# CPLD.net
KiCad netlist of a schematic drawn in Altium Designer
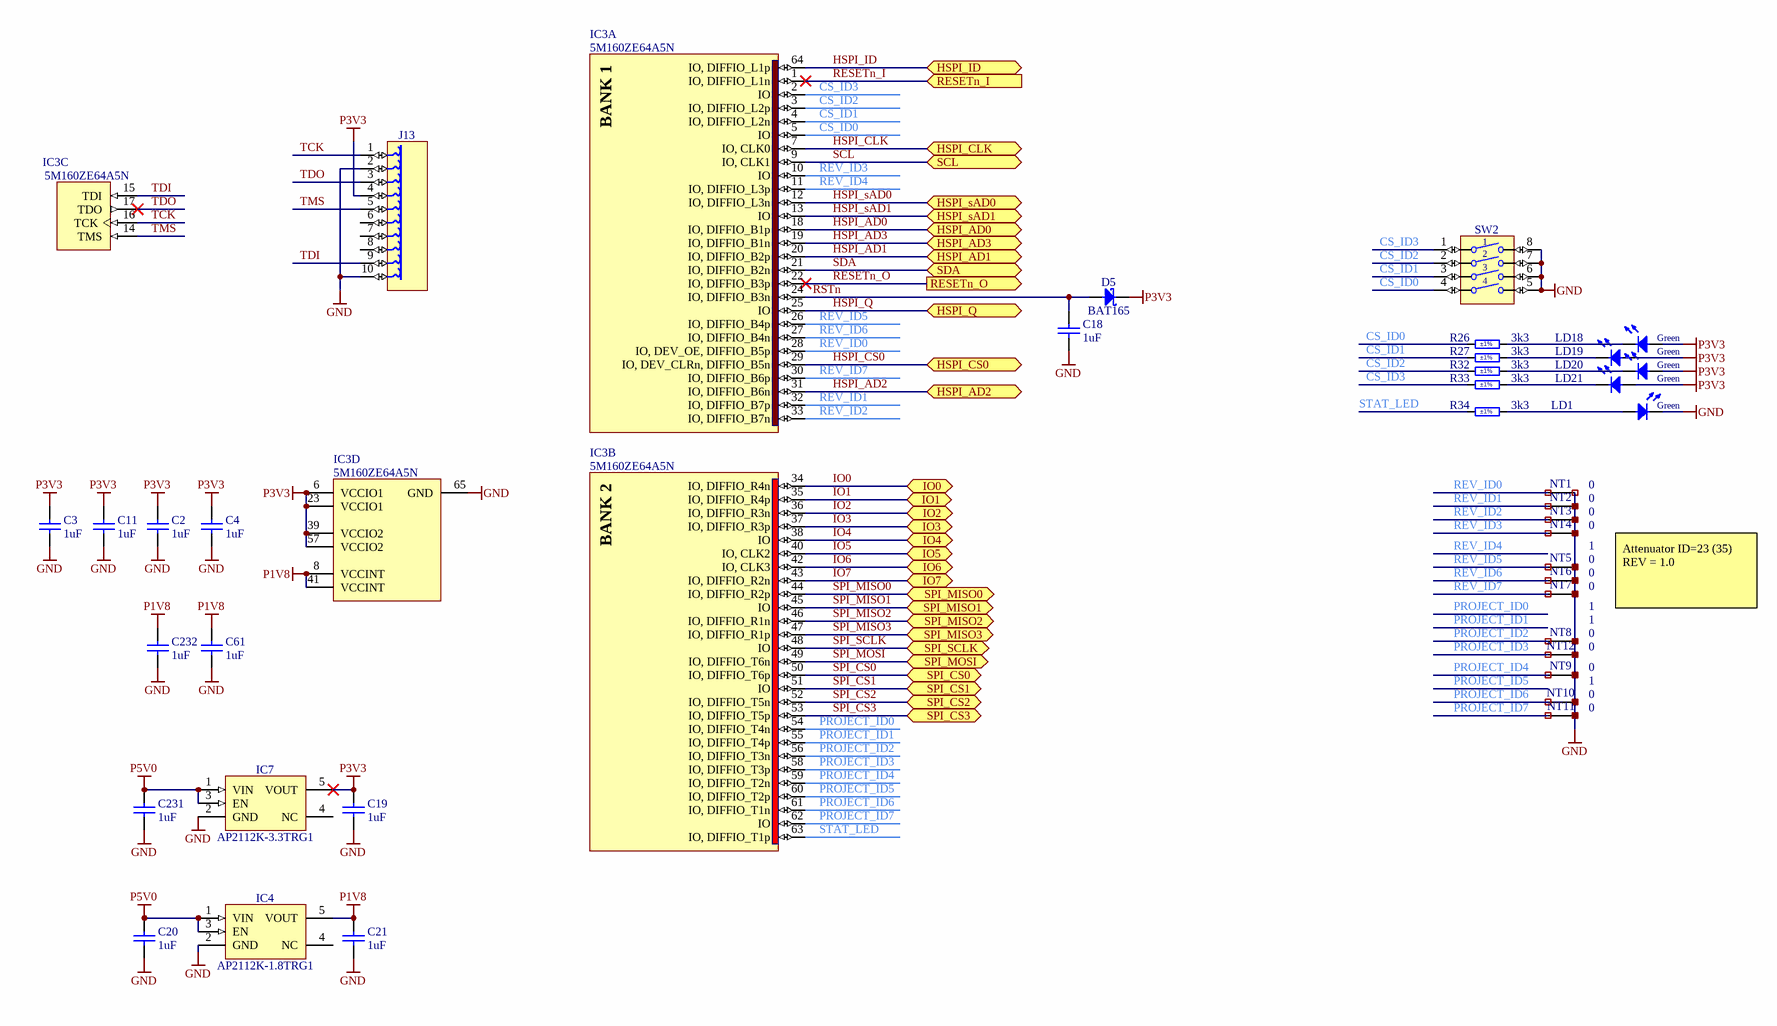
[diagram p0: CPLD.SchDoc]

(export (version "E")
  (design (tool "Eeschema 10.0.6"))
  (components
    (comp (ref "C2")
      (value "1uF")
      (footprint "CAPC1005X55N")
      (description "Non-polarised capacitor")
      (fields
        (field (name "PART NUMBER") "CC0402_1UF_16V_10%_X5R")
        (field (name "VOLTAGE") "16V")
        (field (name "AUTHOR") "CERN DEM JLC")
      )
      (libsource (lib "Capacitors") (part "Capacitor - non polarized"))
    )
    (comp (ref "C3")
      (value "1uF")
      (footprint "CAPC1005X55N")
      (description "Non-polarised capacitor")
      (fields
        (field (name "PART NUMBER") "CC0402_1UF_16V_10%_X5R")
        (field (name "VOLTAGE") "16V")
        (field (name "AUTHOR") "CERN DEM JLC")
      )
      (libsource (lib "Capacitors") (part "Capacitor - non polarized"))
    )
    (comp (ref "C4")
      (value "1uF")
      (footprint "CAPC1005X55N")
      (description "Non-polarised capacitor")
      (fields
        (field (name "PART NUMBER") "CC0402_1UF_16V_10%_X5R")
        (field (name "VOLTAGE") "16V")
        (field (name "AUTHOR") "CERN DEM JLC")
      )
      (libsource (lib "Capacitors") (part "Capacitor - non polarized"))
    )
    (comp (ref "C11")
      (value "1uF")
      (footprint "CAPC1005X55N")
      (description "Non-polarised capacitor")
      (fields
        (field (name "PART NUMBER") "CC0402_1UF_16V_10%_X5R")
        (field (name "VOLTAGE") "16V")
        (field (name "AUTHOR") "CERN DEM JLC")
      )
      (libsource (lib "Capacitors") (part "Capacitor - non polarized"))
    )
    (comp (ref "C18")
      (value "1uF")
      (footprint "CAPC1005X55N")
      (description "Non-polarised capacitor")
      (fields
        (field (name "PART NUMBER") "CC0402_1UF_16V_10%_X5R")
        (field (name "VOLTAGE") "16V")
        (field (name "AUTHOR") "CERN DEM JLC")
      )
      (libsource (lib "Capacitors") (part "Capacitor - non polarized"))
    )
    (comp (ref "C19")
      (value "1uF")
      (footprint "CAPC1005X55N")
      (description "Non-polarised capacitor")
      (fields
        (field (name "PART NUMBER") "CC0402_1UF_16V_10%_X5R")
        (field (name "VOLTAGE") "16V")
        (field (name "AUTHOR") "CERN DEM JLC")
      )
      (libsource (lib "Capacitors") (part "Capacitor - non polarized"))
    )
    (comp (ref "C20")
      (value "1uF")
      (footprint "CAPC1005X55N")
      (description "Non-polarised capacitor")
      (fields
        (field (name "PART NUMBER") "CC0402_1UF_16V_10%_X5R")
        (field (name "VOLTAGE") "16V")
        (field (name "AUTHOR") "CERN DEM JLC")
      )
      (libsource (lib "Capacitors") (part "Capacitor - non polarized"))
    )
    (comp (ref "C21")
      (value "1uF")
      (footprint "CAPC1005X55N")
      (description "Non-polarised capacitor")
      (fields
        (field (name "PART NUMBER") "CC0402_1UF_16V_10%_X5R")
        (field (name "VOLTAGE") "16V")
        (field (name "AUTHOR") "CERN DEM JLC")
      )
      (libsource (lib "Capacitors") (part "Capacitor - non polarized"))
    )
    (comp (ref "C61")
      (value "1uF")
      (footprint "CAPC1005X55N")
      (description "Non-polarised capacitor")
      (fields
        (field (name "PART NUMBER") "CC0402_1UF_16V_10%_X5R")
        (field (name "VOLTAGE") "16V")
        (field (name "AUTHOR") "CERN DEM JLC")
      )
      (libsource (lib "Capacitors") (part "Capacitor - non polarized"))
    )
    (comp (ref "C231")
      (value "1uF")
      (footprint "CAPC1005X55N")
      (description "Non-polarised capacitor")
      (fields
        (field (name "PART NUMBER") "CC0402_1UF_16V_10%_X5R")
        (field (name "VOLTAGE") "16V")
        (field (name "AUTHOR") "CERN DEM JLC")
      )
      (libsource (lib "Capacitors") (part "Capacitor - non polarized"))
    )
    (comp (ref "C232")
      (value "1uF")
      (footprint "CAPC1005X55N")
      (description "Non-polarised capacitor")
      (fields
        (field (name "PART NUMBER") "CC0402_1UF_16V_10%_X5R")
        (field (name "VOLTAGE") "16V")
        (field (name "AUTHOR") "CERN DEM JLC")
      )
      (libsource (lib "Capacitors") (part "Capacitor - non polarized"))
    )
    (comp (ref "D5")
      (value "BAT165")
      (footprint "SOD2512X110N")
      (description "Schottky Diode")
      (fields
        (field (name "VOLTAGE") "40V")
        (field (name "POWER") "750mA")
        (field (name "AUTHOR") "CERN DEM JLC")
      )
      (libsource (lib "ICs And Semiconductors") (part "Diode Schottky"))
    )
    (comp (ref "IC3")
      (value "5M160ZE64A5N")
      (footprint "QFP40P900X900X120-65N-S550")
      (fields (field (name "MANUFACTURER") "ALTERA") (field (name "AUTHOR") "CERN DEM JLC"))
      (libsource (lib "") (part "5M160ZE64A5N_1"))
    )
    (comp (ref "IC4")
      (value "AP2112K-1.8TRG1")
      (footprint "SOT95P285X140-5N")
      (description "600mA CMOS Low Dropout Linear Regulator with Enable")
      (fields
        (field (name "MANUFACTURER") "DIODES INCORPORATED")
        (field (name "MANUFACTURER PART NUMBER") "AP2112K-1.8")
        (field (name "AUTHOR") "CERN DEM JLC")
      )
      (libsource (lib "ICs And Semiconductors") (part "AP2112K"))
    )
    (comp (ref "IC7")
      (value "AP2112K-3.3TRG1")
      (footprint "SOT95P285X140-5N")
      (description "600mA CMOS Low Dropout Linear Regulator with Enable")
      (fields
        (field (name "MANUFACTURER") "DIODES INCORPORATED")
        (field (name "MANUFACTURER PART NUMBER") "AP2112K-3.3")
        (field (name "AUTHOR") "CERN DEM MR")
      )
      (libsource (lib "ICs And Semiconductors") (part "AP2112K"))
    )
    (comp (ref "J13")
      (value "TC2050-IDC")
      (footprint "TC2050-IDC")
      (description "TC2030-MCP and TC2050-IDC Pad Contact")
      (fields (field (name "AUTHOR") "CERN DEM HF"))
      (libsource (lib "Eletro-mechanical") (part "TC2050-IDC"))
    )
    (comp (ref "LD1")
      (value "Green")
      (footprint "LED_KINGBRIGHT_KP-1608CGCK")
      (description "LED Green 1C 2A")
      (fields
        (field (name "PART NUMBER") "LED_KINGBRIGHT_KP-1608CGCK")
        (field (name "MANUFACTURER") "KINGBRIGHT")
        (field (name "AUTHOR") "CERN DEM HF")
      )
      (libsource (lib "ICs And Semiconductors") (part "LED Green 1C 2A"))
    )
    (comp (ref "LD18")
      (value "Green")
      (footprint "LED_KINGBRIGHT_KP-1608CGCK")
      (description "LED Green 1C 2A")
      (fields
        (field (name "PART NUMBER") "LED_KINGBRIGHT_KP-1608CGCK")
        (field (name "MANUFACTURER") "KINGBRIGHT")
        (field (name "AUTHOR") "CERN DEM HF")
      )
      (libsource (lib "ICs And Semiconductors") (part "LED Green 1C 2A"))
    )
    (comp (ref "LD19")
      (value "Green")
      (footprint "LED_KINGBRIGHT_KP-1608CGCK")
      (description "LED Green 1C 2A")
      (fields
        (field (name "PART NUMBER") "LED_KINGBRIGHT_KP-1608CGCK")
        (field (name "MANUFACTURER") "KINGBRIGHT")
        (field (name "AUTHOR") "CERN DEM HF")
      )
      (libsource (lib "ICs And Semiconductors") (part "LED Green 1C 2A"))
    )
    (comp (ref "LD20")
      (value "Green")
      (footprint "LED_KINGBRIGHT_KP-1608CGCK")
      (description "LED Green 1C 2A")
      (fields
        (field (name "PART NUMBER") "LED_KINGBRIGHT_KP-1608CGCK")
        (field (name "MANUFACTURER") "KINGBRIGHT")
        (field (name "AUTHOR") "CERN DEM HF")
      )
      (libsource (lib "ICs And Semiconductors") (part "LED Green 1C 2A"))
    )
    (comp (ref "LD21")
      (value "Green")
      (footprint "LED_KINGBRIGHT_KP-1608CGCK")
      (description "LED Green 1C 2A")
      (fields
        (field (name "PART NUMBER") "LED_KINGBRIGHT_KP-1608CGCK")
        (field (name "MANUFACTURER") "KINGBRIGHT")
        (field (name "AUTHOR") "CERN DEM HF")
      )
      (libsource (lib "ICs And Semiconductors") (part "LED Green 1C 2A"))
    )
    (comp (ref "NT1")
      (value "Net Tie")
      (footprint "Net Tie 3")
      (fields (field (name "PART NUMBER") "Net Tie 3") (field (name "AUTHOR") "CERN DEM HF"))
      (libsource (lib "Eletro-mechanical") (part "Net Tie_a"))
    )
    (comp (ref "NT2")
      (value "Net Tie")
      (footprint "Net Tie 3")
      (fields (field (name "PART NUMBER") "Net Tie 3") (field (name "AUTHOR") "CERN DEM HF"))
      (libsource (lib "Eletro-mechanical") (part "Net Tie_a"))
    )
    (comp (ref "NT3")
      (value "Net Tie")
      (footprint "Net Tie 3")
      (fields (field (name "PART NUMBER") "Net Tie 3") (field (name "AUTHOR") "CERN DEM HF"))
      (libsource (lib "Eletro-mechanical") (part "Net Tie_a"))
    )
    (comp (ref "NT4")
      (value "Net Tie")
      (footprint "Net Tie 3")
      (fields (field (name "PART NUMBER") "Net Tie 3") (field (name "AUTHOR") "CERN DEM HF"))
      (libsource (lib "Eletro-mechanical") (part "Net Tie_a"))
    )
    (comp (ref "NT5")
      (value "Net Tie")
      (footprint "Net Tie 3")
      (fields (field (name "PART NUMBER") "Net Tie 3") (field (name "AUTHOR") "CERN DEM HF"))
      (libsource (lib "Eletro-mechanical") (part "Net Tie_a"))
    )
    (comp (ref "NT6")
      (value "Net Tie")
      (footprint "Net Tie 3")
      (fields (field (name "PART NUMBER") "Net Tie 3") (field (name "AUTHOR") "CERN DEM HF"))
      (libsource (lib "Eletro-mechanical") (part "Net Tie_a"))
    )
    (comp (ref "NT7")
      (value "Net Tie")
      (footprint "Net Tie 3")
      (fields (field (name "PART NUMBER") "Net Tie 3") (field (name "AUTHOR") "CERN DEM HF"))
      (libsource (lib "Eletro-mechanical") (part "Net Tie_a"))
    )
    (comp (ref "NT8")
      (value "Net Tie")
      (footprint "Net Tie 3")
      (fields (field (name "PART NUMBER") "Net Tie 3") (field (name "AUTHOR") "CERN DEM HF"))
      (libsource (lib "Eletro-mechanical") (part "Net Tie_a"))
    )
    (comp (ref "NT9")
      (value "Net Tie")
      (footprint "Net Tie 3")
      (fields (field (name "PART NUMBER") "Net Tie 3") (field (name "AUTHOR") "CERN DEM HF"))
      (libsource (lib "Eletro-mechanical") (part "Net Tie_a"))
    )
    (comp (ref "NT10")
      (value "Net Tie")
      (footprint "Net Tie 3")
      (fields (field (name "PART NUMBER") "Net Tie 3") (field (name "AUTHOR") "CERN DEM HF"))
      (libsource (lib "Eletro-mechanical") (part "Net Tie_a"))
    )
    (comp (ref "NT11")
      (value "Net Tie")
      (footprint "Net Tie 3")
      (fields (field (name "PART NUMBER") "Net Tie 3") (field (name "AUTHOR") "CERN DEM HF"))
      (libsource (lib "Eletro-mechanical") (part "Net Tie_a"))
    )
    (comp (ref "NT12")
      (value "Net Tie")
      (footprint "Net Tie 3")
      (fields (field (name "PART NUMBER") "Net Tie 3") (field (name "AUTHOR") "CERN DEM HF"))
      (libsource (lib "Eletro-mechanical") (part "Net Tie_a"))
    )
    (comp (ref "R26")
      (value "3k3")
      (footprint "RESC1005X40N")
      (description "Resistor - 1%")
      (fields
        (field (name "TOLERANCE") "±1%")
        (field (name "PART NUMBER") "R0402_3K3_1%_0.0625W_100PPM")
        (field (name "POWER") "0.0625W")
        (field (name "AUTHOR") "CERN DEM JLC")
      )
      (libsource (lib "Resistors") (part "Resistor - 1%"))
    )
    (comp (ref "R27")
      (value "3k3")
      (footprint "RESC1005X40N")
      (description "Resistor - 1%")
      (fields
        (field (name "TOLERANCE") "±1%")
        (field (name "PART NUMBER") "R0402_3K3_1%_0.0625W_100PPM")
        (field (name "POWER") "0.0625W")
        (field (name "AUTHOR") "CERN DEM JLC")
      )
      (libsource (lib "Resistors") (part "Resistor - 1%"))
    )
    (comp (ref "R32")
      (value "3k3")
      (footprint "RESC1005X40N")
      (description "Resistor - 1%")
      (fields
        (field (name "TOLERANCE") "±1%")
        (field (name "PART NUMBER") "R0402_3K3_1%_0.0625W_100PPM")
        (field (name "POWER") "0.0625W")
        (field (name "AUTHOR") "CERN DEM JLC")
      )
      (libsource (lib "Resistors") (part "Resistor - 1%"))
    )
    (comp (ref "R33")
      (value "3k3")
      (footprint "RESC1005X40N")
      (description "Resistor - 1%")
      (fields
        (field (name "TOLERANCE") "±1%")
        (field (name "PART NUMBER") "R0402_3K3_1%_0.0625W_100PPM")
        (field (name "POWER") "0.0625W")
        (field (name "AUTHOR") "CERN DEM JLC")
      )
      (libsource (lib "Resistors") (part "Resistor - 1%"))
    )
    (comp (ref "R34")
      (value "3k3")
      (footprint "RESC1005X40N")
      (description "Resistor - 1%")
      (fields
        (field (name "TOLERANCE") "±1%")
        (field (name "PART NUMBER") "R0402_3K3_1%_0.0625W_100PPM")
        (field (name "POWER") "0.0625W")
        (field (name "AUTHOR") "CERN DEM JLC")
      )
      (libsource (lib "Resistors") (part "Resistor - 1%"))
    )
    (comp (ref "SW2")
      (value "Switch")
      (footprint "SW_OMRON_A6H-4102")
      (description "4 Ways SPST DIP Switch")
      (fields
        (field (name "PART NUMBER") "SW_OMRON_A6H-4102")
        (field (name "MANUFACTURER") "OMRON")
        (field (name "AUTHOR") "CERN DEM JLC")
      )
      (libsource (lib "Eletro-mechanical") (part "SW 4x SPST DIP Switch"))
    )
  )
  (nets
    (net (code "1") (name "/CS_ID0") (class "Default")
      (node (ref "IC3") (pin "5") (pinfunction "IO_5") (pintype "bidirectional"))
      (node (ref "R26") (pin "2") (pinfunction "2_2") (pintype "passive"))
      (node (ref "SW2") (pin "4") (pinfunction "4_4") (pintype "bidirectional"))
    )
    (net (code "2") (name "/CS_ID1") (class "Default")
      (node (ref "IC3") (pin "4") (pinfunction "IO,_DIFFIO_L2n_4") (pintype "bidirectional"))
      (node (ref "R27") (pin "2") (pinfunction "2_2") (pintype "passive"))
      (node (ref "SW2") (pin "3") (pinfunction "3_3") (pintype "bidirectional"))
    )
    (net (code "3") (name "/CS_ID2") (class "Default")
      (node (ref "IC3") (pin "3") (pinfunction "IO,_DIFFIO_L2p_3") (pintype "bidirectional"))
      (node (ref "R32") (pin "2") (pinfunction "2_2") (pintype "passive"))
      (node (ref "SW2") (pin "2") (pinfunction "2_2") (pintype "bidirectional"))
    )
    (net (code "4") (name "/CS_ID3") (class "Default")
      (node (ref "IC3") (pin "2") (pinfunction "IO_2") (pintype "bidirectional"))
      (node (ref "R33") (pin "2") (pinfunction "2_2") (pintype "passive"))
      (node (ref "SW2") (pin "1") (pinfunction "1_1") (pintype "bidirectional"))
    )
    (net (code "5") (name "/HSPI_AD0") (class "Default")
      (node (ref "IC3") (pin "18") (pinfunction "IO,_DIFFIO_B1p_18") (pintype "bidirectional"))
    )
    (net (code "6") (name "/HSPI_AD1") (class "Default")
      (node (ref "IC3") (pin "20") (pinfunction "IO,_DIFFIO_B2p_20") (pintype "bidirectional"))
    )
    (net (code "7") (name "/HSPI_AD2") (class "Default")
      (node (ref "IC3") (pin "31") (pinfunction "IO,_DIFFIO_B6n_31") (pintype "bidirectional"))
    )
    (net (code "8") (name "/HSPI_AD3") (class "Default")
      (node (ref "IC3") (pin "19") (pinfunction "IO,_DIFFIO_B1n_19") (pintype "bidirectional"))
    )
    (net (code "9") (name "/HSPI_CLK") (class "Default")
      (node (ref "IC3") (pin "7") (pinfunction "IO,_CLK0_7") (pintype "bidirectional"))
    )
    (net (code "10") (name "/HSPI_CS0") (class "Default")
      (node (ref "IC3") (pin "29") (pinfunction "IO,_DEV_CLRn,_DIFFIO_B5n_29") (pintype "bidirectional"))
    )
    (net (code "11") (name "/HSPI_ID") (class "Default")
      (node (ref "IC3") (pin "64") (pinfunction "IO,_DIFFIO_L1p_64") (pintype "bidirectional"))
    )
    (net (code "12") (name "/HSPI_Q") (class "Default")
      (node (ref "IC3") (pin "25") (pinfunction "IO_25") (pintype "bidirectional"))
    )
    (net (code "13") (name "/HSPI_sAD0") (class "Default")
      (node (ref "IC3") (pin "12") (pinfunction "IO,_DIFFIO_L3n_12") (pintype "bidirectional"))
    )
    (net (code "14") (name "/HSPI_sAD1") (class "Default")
      (node (ref "IC3") (pin "13") (pinfunction "IO_13") (pintype "bidirectional"))
    )
    (net (code "15") (name "/IO0") (class "Default")
      (node (ref "IC3") (pin "34") (pinfunction "IO,_DIFFIO_R4n_34") (pintype "bidirectional"))
    )
    (net (code "16") (name "/IO1") (class "Default")
      (node (ref "IC3") (pin "35") (pinfunction "IO,_DIFFIO_R4p_35") (pintype "bidirectional"))
    )
    (net (code "17") (name "/IO2") (class "Default")
      (node (ref "IC3") (pin "36") (pinfunction "IO,_DIFFIO_R3n_36") (pintype "bidirectional"))
    )
    (net (code "18") (name "/IO3") (class "Default")
      (node (ref "IC3") (pin "37") (pinfunction "IO,_DIFFIO_R3p_37") (pintype "bidirectional"))
    )
    (net (code "19") (name "/IO4") (class "Default")
      (node (ref "IC3") (pin "38") (pinfunction "IO_38") (pintype "bidirectional"))
    )
    (net (code "20") (name "/IO5") (class "Default")
      (node (ref "IC3") (pin "40") (pinfunction "IO,_CLK2_40") (pintype "bidirectional"))
    )
    (net (code "21") (name "/IO6") (class "Default")
      (node (ref "IC3") (pin "42") (pinfunction "IO,_CLK3_42") (pintype "bidirectional"))
    )
    (net (code "22") (name "/IO7") (class "Default")
      (node (ref "IC3") (pin "43") (pinfunction "IO,_DIFFIO_R2n_43") (pintype "bidirectional"))
    )
    (net (code "23") (name "/PROJECT_ID0") (class "Default")
      (node (ref "IC3") (pin "54") (pinfunction "IO,_DIFFIO_T4n_54") (pintype "bidirectional"))
    )
    (net (code "24") (name "/PROJECT_ID1") (class "Default")
      (node (ref "IC3") (pin "55") (pinfunction "IO,_DIFFIO_T4p_55") (pintype "bidirectional"))
    )
    (net (code "25") (name "/PROJECT_ID2") (class "Default")
      (node (ref "IC3") (pin "56") (pinfunction "IO,_DIFFIO_T3n_56") (pintype "bidirectional"))
      (node (ref "NT8") (pin "1") (pinfunction "1_1") (pintype "bidirectional"))
    )
    (net (code "26") (name "/PROJECT_ID3") (class "Default")
      (node (ref "IC3") (pin "58") (pinfunction "IO,_DIFFIO_T3p_58") (pintype "bidirectional"))
      (node (ref "NT12") (pin "1") (pinfunction "1_1") (pintype "bidirectional"))
    )
    (net (code "27") (name "/PROJECT_ID4") (class "Default")
      (node (ref "IC3") (pin "59") (pinfunction "IO,_DIFFIO_T2n_59") (pintype "bidirectional"))
      (node (ref "NT9") (pin "1") (pinfunction "1_1") (pintype "bidirectional"))
    )
    (net (code "28") (name "/PROJECT_ID5") (class "Default")
      (node (ref "IC3") (pin "60") (pinfunction "IO,_DIFFIO_T2p_60") (pintype "bidirectional"))
    )
    (net (code "29") (name "/PROJECT_ID6") (class "Default")
      (node (ref "IC3") (pin "61") (pinfunction "IO,_DIFFIO_T1n_61") (pintype "bidirectional"))
      (node (ref "NT10") (pin "1") (pinfunction "1_1") (pintype "bidirectional"))
    )
    (net (code "30") (name "/PROJECT_ID7") (class "Default")
      (node (ref "IC3") (pin "62") (pinfunction "IO_62") (pintype "bidirectional"))
      (node (ref "NT11") (pin "1") (pinfunction "1_1") (pintype "bidirectional"))
    )
    (net (code "31") (name "/RESETn_I") (class "Default")
      (node (ref "IC3") (pin "1") (pinfunction "IO,_DIFFIO_L1n_1") (pintype "bidirectional+no_connect"))
    )
    (net (code "32") (name "/RESETn_O") (class "Default")
      (node (ref "IC3") (pin "22") (pinfunction "IO,_DIFFIO_B3p_22") (pintype "bidirectional+no_connect"))
    )
    (net (code "33") (name "/REV_ID0") (class "Default")
      (node (ref "IC3") (pin "28") (pinfunction "IO,_DEV_OE,_DIFFIO_B5p_28") (pintype "bidirectional"))
      (node (ref "NT1") (pin "1") (pinfunction "1_1") (pintype "bidirectional"))
    )
    (net (code "34") (name "/REV_ID1") (class "Default")
      (node (ref "IC3") (pin "32") (pinfunction "IO,_DIFFIO_B7p_32") (pintype "bidirectional"))
      (node (ref "NT2") (pin "1") (pinfunction "1_1") (pintype "bidirectional"))
    )
    (net (code "35") (name "/REV_ID2") (class "Default")
      (node (ref "IC3") (pin "33") (pinfunction "IO,_DIFFIO_B7n_33") (pintype "bidirectional"))
      (node (ref "NT3") (pin "1") (pinfunction "1_1") (pintype "bidirectional"))
    )
    (net (code "36") (name "/REV_ID3") (class "Default")
      (node (ref "IC3") (pin "10") (pinfunction "IO_10") (pintype "bidirectional"))
      (node (ref "NT4") (pin "1") (pinfunction "1_1") (pintype "bidirectional"))
    )
    (net (code "37") (name "/REV_ID4") (class "Default")
      (node (ref "IC3") (pin "11") (pinfunction "IO,_DIFFIO_L3p_11") (pintype "bidirectional"))
    )
    (net (code "38") (name "/REV_ID5") (class "Default")
      (node (ref "IC3") (pin "26") (pinfunction "IO,_DIFFIO_B4p_26") (pintype "bidirectional"))
      (node (ref "NT5") (pin "1") (pinfunction "1_1") (pintype "bidirectional"))
    )
    (net (code "39") (name "/REV_ID6") (class "Default")
      (node (ref "IC3") (pin "27") (pinfunction "IO,_DIFFIO_B4n_27") (pintype "bidirectional"))
      (node (ref "NT6") (pin "1") (pinfunction "1_1") (pintype "bidirectional"))
    )
    (net (code "40") (name "/REV_ID7") (class "Default")
      (node (ref "IC3") (pin "30") (pinfunction "IO,_DIFFIO_B6p_30") (pintype "bidirectional"))
      (node (ref "NT7") (pin "1") (pinfunction "1_1") (pintype "bidirectional"))
    )
    (net (code "41") (name "/RSTn") (class "Default")
      (node (ref "C18") (pin "2") (pinfunction "2_2") (pintype "passive"))
      (node (ref "D5") (pin "2") (pinfunction "A_2") (pintype "passive"))
      (node (ref "IC3") (pin "24") (pinfunction "IO,_DIFFIO_B3n_24") (pintype "bidirectional"))
    )
    (net (code "42") (name "/SCL") (class "Default")
      (node (ref "IC3") (pin "9") (pinfunction "IO,_CLK1_9") (pintype "bidirectional"))
    )
    (net (code "43") (name "/SDA") (class "Default")
      (node (ref "IC3") (pin "21") (pinfunction "IO,_DIFFIO_B2n_21") (pintype "bidirectional"))
    )
    (net (code "44") (name "/SPI_CS0") (class "Default")
      (node (ref "IC3") (pin "50") (pinfunction "IO,_DIFFIO_T6p_50") (pintype "bidirectional"))
    )
    (net (code "45") (name "/SPI_CS1") (class "Default")
      (node (ref "IC3") (pin "51") (pinfunction "IO_51") (pintype "bidirectional"))
    )
    (net (code "46") (name "/SPI_CS2") (class "Default")
      (node (ref "IC3") (pin "52") (pinfunction "IO,_DIFFIO_T5n_52") (pintype "bidirectional"))
    )
    (net (code "47") (name "/SPI_CS3") (class "Default")
      (node (ref "IC3") (pin "53") (pinfunction "IO,_DIFFIO_T5p_53") (pintype "bidirectional"))
    )
    (net (code "48") (name "/SPI_MISO0") (class "Default")
      (node (ref "IC3") (pin "44") (pinfunction "IO,_DIFFIO_R2p_44") (pintype "bidirectional"))
    )
    (net (code "49") (name "/SPI_MISO1") (class "Default")
      (node (ref "IC3") (pin "45") (pinfunction "IO_45") (pintype "bidirectional"))
    )
    (net (code "50") (name "/SPI_MISO2") (class "Default")
      (node (ref "IC3") (pin "46") (pinfunction "IO,_DIFFIO_R1n_46") (pintype "bidirectional"))
    )
    (net (code "51") (name "/SPI_MISO3") (class "Default")
      (node (ref "IC3") (pin "47") (pinfunction "IO,_DIFFIO_R1p_47") (pintype "bidirectional"))
    )
    (net (code "52") (name "/SPI_MOSI") (class "Default")
      (node (ref "IC3") (pin "49") (pinfunction "IO,_DIFFIO_T6n_49") (pintype "bidirectional"))
    )
    (net (code "53") (name "/SPI_SCLK") (class "Default")
      (node (ref "IC3") (pin "48") (pinfunction "IO_48") (pintype "bidirectional"))
    )
    (net (code "54") (name "/STAT_LED") (class "Default")
      (node (ref "IC3") (pin "63") (pinfunction "IO,_DIFFIO_T1p_63") (pintype "bidirectional"))
      (node (ref "R34") (pin "2") (pinfunction "2_2") (pintype "passive"))
    )
    (net (code "55") (name "/TCK") (class "Default")
      (node (ref "IC3") (pin "16") (pinfunction "TCK_16") (pintype "input"))
      (node (ref "J13") (pin "1") (pinfunction "1_1") (pintype "bidirectional"))
    )
    (net (code "56") (name "/TDI") (class "Default")
      (node (ref "IC3") (pin "15") (pinfunction "TDI_15") (pintype "input"))
      (node (ref "J13") (pin "9") (pinfunction "9_9") (pintype "bidirectional"))
    )
    (net (code "57") (name "/TDO") (class "Default")
      (node (ref "IC3") (pin "17") (pinfunction "TDO_17") (pintype "output"))
      (node (ref "J13") (pin "3") (pinfunction "3_3") (pintype "bidirectional"))
    )
    (net (code "58") (name "/TMS") (class "Default")
      (node (ref "IC3") (pin "14") (pinfunction "TMS_14") (pintype "input"))
      (node (ref "J13") (pin "5") (pinfunction "5_5") (pintype "bidirectional"))
    )
    (net (code "59") (name "GND") (class "Default")
      (node (ref "C11") (pin "1") (pinfunction "1_1") (pintype "passive"))
      (node (ref "C18") (pin "1") (pinfunction "1_1") (pintype "passive"))
      (node (ref "C19") (pin "1") (pinfunction "1_1") (pintype "passive"))
      (node (ref "C2") (pin "1") (pinfunction "1_1") (pintype "passive"))
      (node (ref "C20") (pin "1") (pinfunction "1_1") (pintype "passive"))
      (node (ref "C21") (pin "1") (pinfunction "1_1") (pintype "passive"))
      (node (ref "C231") (pin "1") (pinfunction "1_1") (pintype "passive"))
      (node (ref "C232") (pin "1") (pinfunction "1_1") (pintype "passive"))
      (node (ref "C3") (pin "1") (pinfunction "1_1") (pintype "passive"))
      (node (ref "C4") (pin "1") (pinfunction "1_1") (pintype "passive"))
      (node (ref "C61") (pin "1") (pinfunction "1_1") (pintype "passive"))
      (node (ref "IC3") (pin "65") (pinfunction "GND_65") (pintype "power_in"))
      (node (ref "IC4") (pin "2") (pinfunction "GND_2") (pintype "power_in"))
      (node (ref "IC7") (pin "2") (pinfunction "GND_2") (pintype "power_in"))
      (node (ref "J13") (pin "10") (pinfunction "10_10") (pintype "bidirectional"))
      (node (ref "J13") (pin "2") (pinfunction "2_2") (pintype "bidirectional"))
      (node (ref "LD1") (pin "1") (pinfunction "C_1") (pintype "passive"))
      (node (ref "NT1") (pin "2") (pinfunction "2_2") (pintype "bidirectional"))
      (node (ref "NT10") (pin "2") (pinfunction "2_2") (pintype "bidirectional"))
      (node (ref "NT11") (pin "2") (pinfunction "2_2") (pintype "bidirectional"))
      (node (ref "NT12") (pin "2") (pinfunction "2_2") (pintype "bidirectional"))
      (node (ref "NT2") (pin "2") (pinfunction "2_2") (pintype "bidirectional"))
      (node (ref "NT3") (pin "2") (pinfunction "2_2") (pintype "bidirectional"))
      (node (ref "NT4") (pin "2") (pinfunction "2_2") (pintype "bidirectional"))
      (node (ref "NT5") (pin "2") (pinfunction "2_2") (pintype "bidirectional"))
      (node (ref "NT6") (pin "2") (pinfunction "2_2") (pintype "bidirectional"))
      (node (ref "NT7") (pin "2") (pinfunction "2_2") (pintype "bidirectional"))
      (node (ref "NT8") (pin "2") (pinfunction "2_2") (pintype "bidirectional"))
      (node (ref "NT9") (pin "2") (pinfunction "2_2") (pintype "bidirectional"))
      (node (ref "SW2") (pin "5") (pinfunction "5_5") (pintype "bidirectional"))
      (node (ref "SW2") (pin "6") (pinfunction "6_6") (pintype "bidirectional"))
      (node (ref "SW2") (pin "7") (pinfunction "7_7") (pintype "bidirectional"))
      (node (ref "SW2") (pin "8") (pinfunction "8_8") (pintype "bidirectional"))
    )
    (net (code "60") (name "Net-(LD1-A)") (class "Default")
      (node (ref "LD1") (pin "2") (pinfunction "A_2") (pintype "passive"))
      (node (ref "R34") (pin "1") (pinfunction "1_1") (pintype "passive"))
    )
    (net (code "61") (name "Net-(LD18-C)") (class "Default")
      (node (ref "LD18") (pin "1") (pinfunction "C_1") (pintype "passive"))
      (node (ref "R26") (pin "1") (pinfunction "1_1") (pintype "passive"))
    )
    (net (code "62") (name "Net-(LD19-C)") (class "Default")
      (node (ref "LD19") (pin "1") (pinfunction "C_1") (pintype "passive"))
      (node (ref "R27") (pin "1") (pinfunction "1_1") (pintype "passive"))
    )
    (net (code "63") (name "Net-(LD20-C)") (class "Default")
      (node (ref "LD20") (pin "1") (pinfunction "C_1") (pintype "passive"))
      (node (ref "R32") (pin "1") (pinfunction "1_1") (pintype "passive"))
    )
    (net (code "64") (name "Net-(LD21-C)") (class "Default")
      (node (ref "LD21") (pin "1") (pinfunction "C_1") (pintype "passive"))
      (node (ref "R33") (pin "1") (pinfunction "1_1") (pintype "passive"))
    )
    (net (code "65") (name "P1V8") (class "Default")
      (node (ref "C21") (pin "2") (pinfunction "2_2") (pintype "passive"))
      (node (ref "C232") (pin "2") (pinfunction "2_2") (pintype "passive"))
      (node (ref "C61") (pin "2") (pinfunction "2_2") (pintype "passive"))
      (node (ref "IC3") (pin "41") (pinfunction "VCCINT_41") (pintype "power_in"))
      (node (ref "IC3") (pin "8") (pinfunction "VCCINT_8") (pintype "power_in"))
      (node (ref "IC4") (pin "5") (pinfunction "VOUT_5") (pintype "power_in"))
    )
    (net (code "66") (name "P3V3") (class "Default")
      (node (ref "C11") (pin "2") (pinfunction "2_2") (pintype "passive"))
      (node (ref "C19") (pin "2") (pinfunction "2_2") (pintype "passive"))
      (node (ref "C2") (pin "2") (pinfunction "2_2") (pintype "passive"))
      (node (ref "C3") (pin "2") (pinfunction "2_2") (pintype "passive"))
      (node (ref "C4") (pin "2") (pinfunction "2_2") (pintype "passive"))
      (node (ref "D5") (pin "1") (pinfunction "C_1") (pintype "passive"))
      (node (ref "IC3") (pin "23") (pinfunction "VCCIO1_23") (pintype "power_in"))
      (node (ref "IC3") (pin "39") (pinfunction "VCCIO2_39") (pintype "power_in"))
      (node (ref "IC3") (pin "57") (pinfunction "VCCIO2_57") (pintype "power_in"))
      (node (ref "IC3") (pin "6") (pinfunction "VCCIO1_6") (pintype "power_in"))
      (node (ref "IC7") (pin "5") (pinfunction "VOUT_5") (pintype "power_in"))
      (node (ref "J13") (pin "4") (pinfunction "4_4") (pintype "bidirectional"))
      (node (ref "LD18") (pin "2") (pinfunction "A_2") (pintype "passive"))
      (node (ref "LD19") (pin "2") (pinfunction "A_2") (pintype "passive"))
      (node (ref "LD20") (pin "2") (pinfunction "A_2") (pintype "passive"))
      (node (ref "LD21") (pin "2") (pinfunction "A_2") (pintype "passive"))
    )
    (net (code "67") (name "P5V0") (class "Default")
      (node (ref "C20") (pin "2") (pinfunction "2_2") (pintype "passive"))
      (node (ref "C231") (pin "2") (pinfunction "2_2") (pintype "passive"))
      (node (ref "IC4") (pin "1") (pinfunction "VIN_1") (pintype "input"))
      (node (ref "IC4") (pin "3") (pinfunction "EN_3") (pintype "input"))
      (node (ref "IC7") (pin "1") (pinfunction "VIN_1") (pintype "input"))
      (node (ref "IC7") (pin "3") (pinfunction "EN_3") (pintype "input"))
    )
    (net (code "68") (name "unconnected-(IC4-NC-Pad4)") (class "Default")
      (node (ref "IC4") (pin "4") (pinfunction "NC_4") (pintype "passive"))
    )
    (net (code "69") (name "unconnected-(IC7-NC-Pad4)") (class "Default")
      (node (ref "IC7") (pin "4") (pinfunction "NC_4") (pintype "passive"))
    )
    (net (code "70") (name "unconnected-(J13-Pad6)") (class "Default")
      (node (ref "J13") (pin "6") (pinfunction "6_6") (pintype "bidirectional"))
    )
    (net (code "71") (name "unconnected-(J13-Pad7)") (class "Default")
      (node (ref "J13") (pin "7") (pinfunction "7_7") (pintype "bidirectional"))
    )
    (net (code "72") (name "unconnected-(J13-Pad8)") (class "Default")
      (node (ref "J13") (pin "8") (pinfunction "8_8") (pintype "bidirectional"))
    )
  )
)
